# Clock_WR.net
KiCad netlist of a schematic drawn in Altium Designer
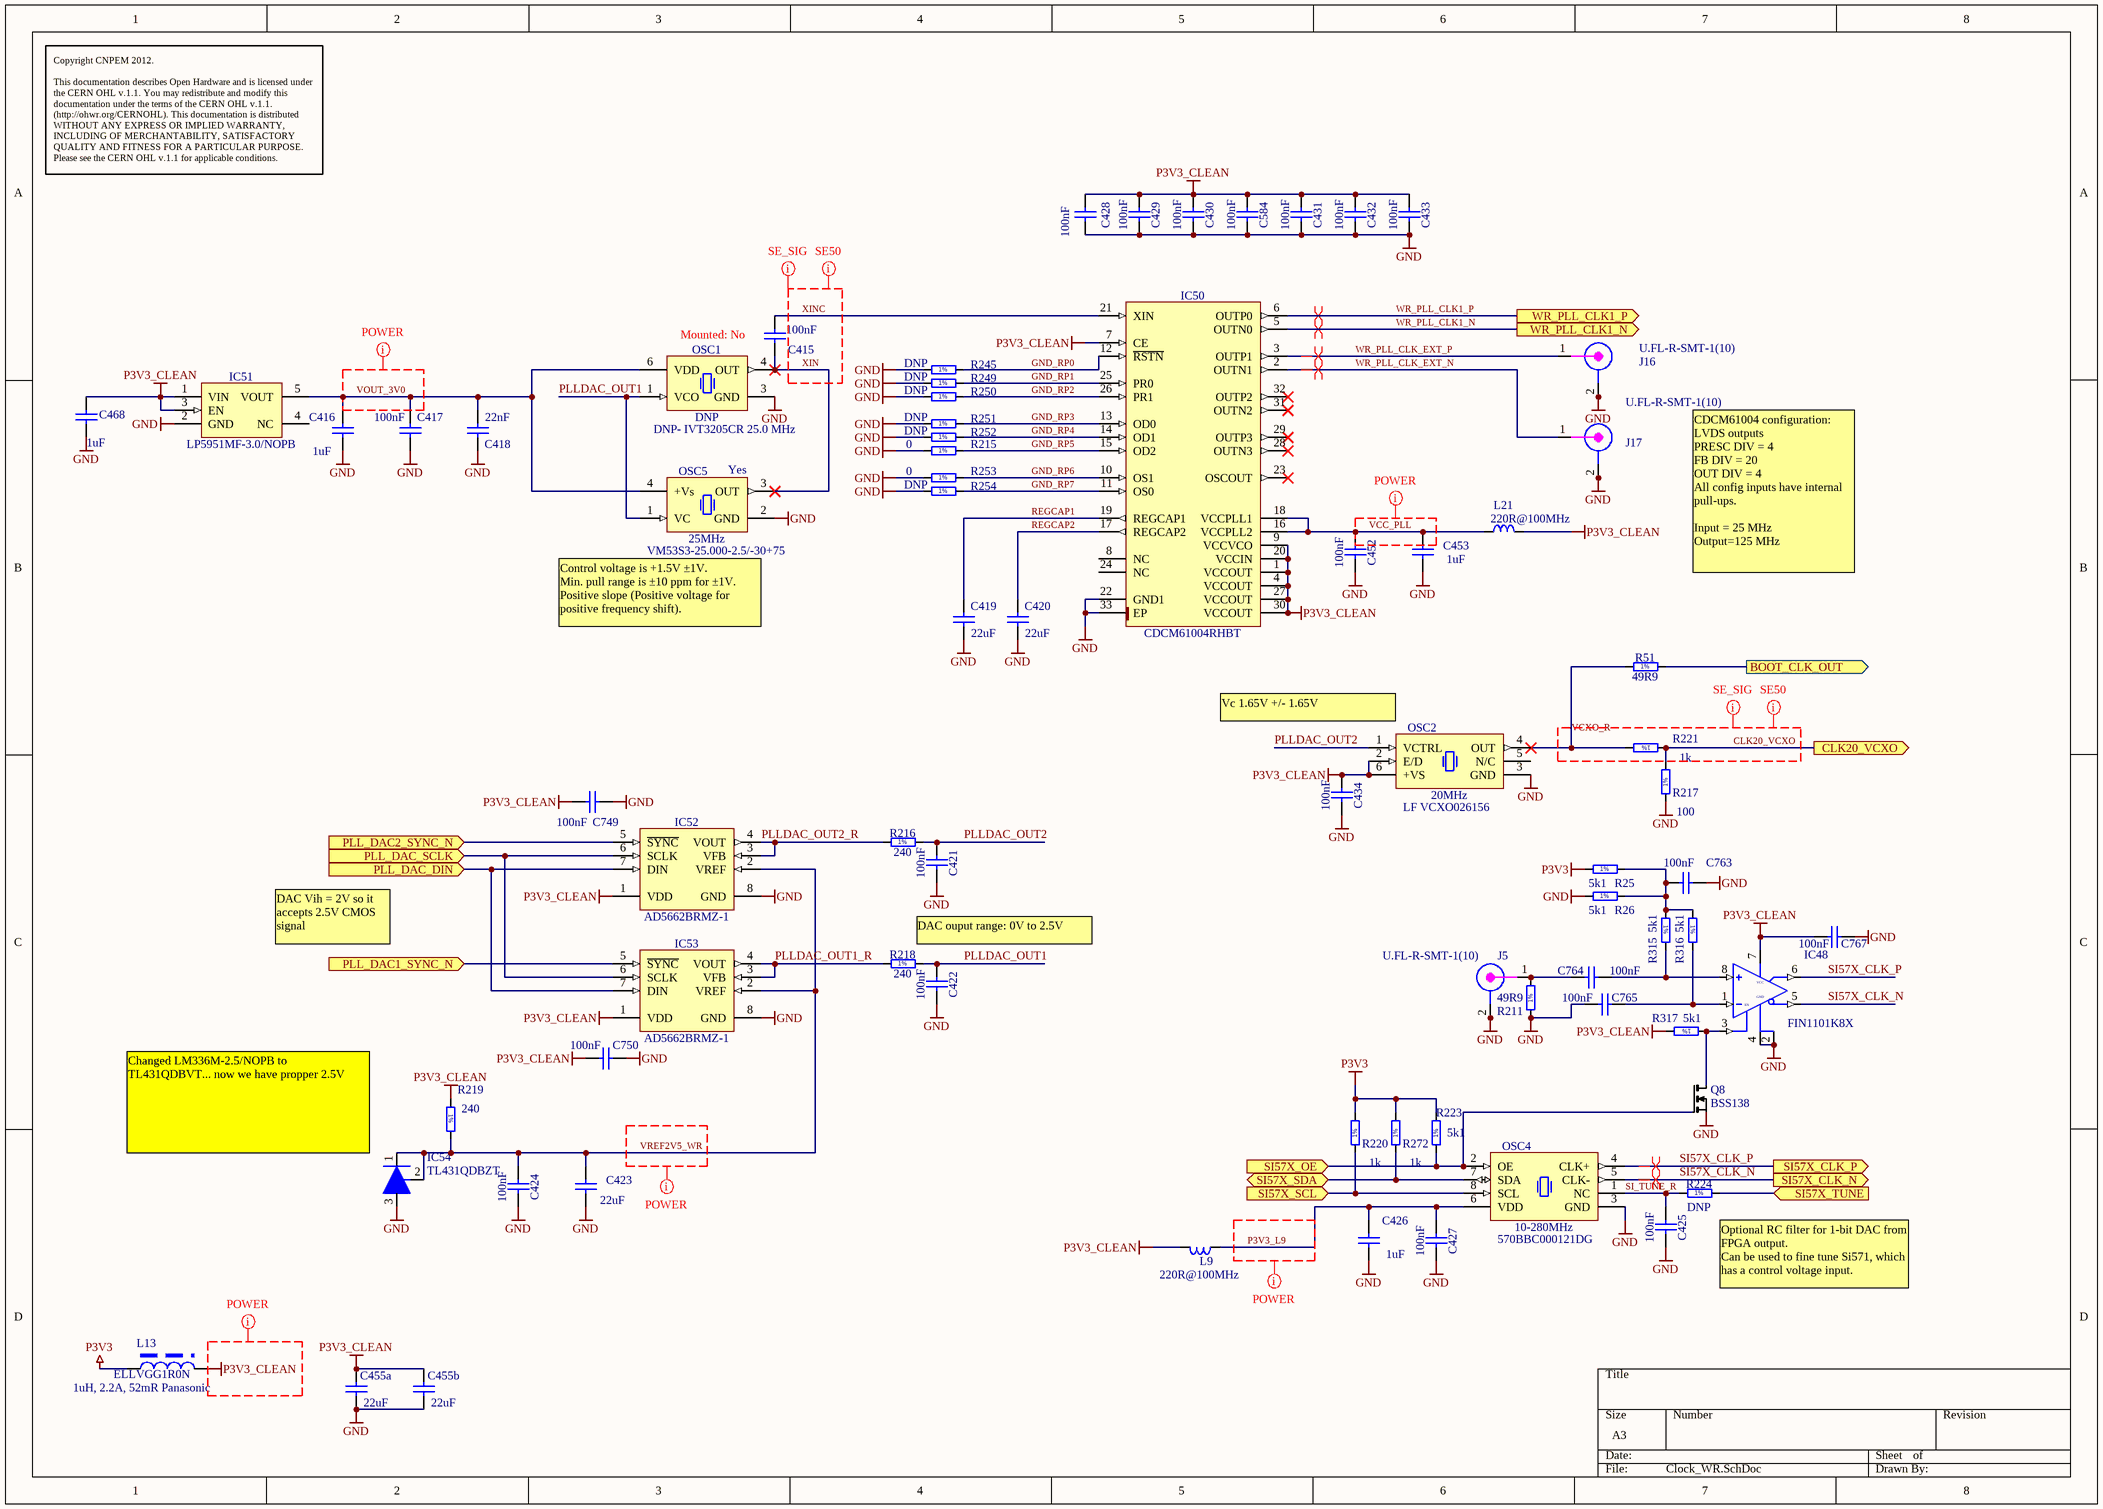
[diagram p0: Clock_WR.SchDoc]

(export (version "E")
  (design (tool "Eeschema 10.0.6"))
  (components
    (comp (ref "C415")
      (value "100nF")
      (footprint "CAPC0603X33N")
      (description "Non-polarised capacitor")
      (fields
        (field (name "PART NUMBER") "CC0201_100NF_6.3V_10%_X5R")
        (field (name "VOLTAGE") "6.3V")
        (field (name "AUTHOR") "CERN DEM JLC")
      )
      (libsource (lib "Capacitors") (part "Capacitor - non polarized"))
    )
    (comp (ref "C416")
      (value "1uF")
      (footprint "CAPC1608X87N")
      (description "Non-polarised capacitor")
      (fields
        (field (name "PART NUMBER") "CC0603_1UF_16V_10%_X7R")
        (field (name "VOLTAGE") "16V")
        (field (name "AUTHOR") "CERN DEM JLC")
      )
      (libsource (lib "Capacitors") (part "Capacitor - non polarized"))
    )
    (comp (ref "C417")
      (value "100nF")
      (footprint "CAPC0603X33N")
      (description "Non-polarised capacitor")
      (fields
        (field (name "PART NUMBER") "CC0201_100NF_6.3V_10%_X5R")
        (field (name "VOLTAGE") "6.3V")
        (field (name "AUTHOR") "CERN DEM JLC")
      )
      (libsource (lib "Capacitors") (part "Capacitor - non polarized"))
    )
    (comp (ref "C418")
      (value "22nF")
      (footprint "CAPC0603X33N")
      (description "Non-polarised capacitor")
      (fields
        (field (name "PART NUMBER") "CC0201_22NF_6.3V_10%_X5R")
        (field (name "VOLTAGE") "6.3V")
        (field (name "AUTHOR") "CERN DEM JLC")
      )
      (libsource (lib "Capacitors") (part "Capacitor - non polarized"))
    )
    (comp (ref "C419")
      (value "22uF")
      (footprint "CAPC3216X180N")
      (description "Non-polarised capacitor")
      (fields
        (field (name "PART NUMBER") "CC1206_22UF_10V_10%_X7R")
        (field (name "VOLTAGE") "10V")
        (field (name "AUTHOR") "CERN DEM JLC")
      )
      (libsource (lib "Capacitors") (part "Capacitor - non polarized"))
    )
    (comp (ref "C420")
      (value "22uF")
      (footprint "CAPC3216X180N")
      (description "Non-polarised capacitor")
      (fields
        (field (name "PART NUMBER") "CC1206_22UF_10V_10%_X7R")
        (field (name "VOLTAGE") "10V")
        (field (name "AUTHOR") "CERN DEM JLC")
      )
      (libsource (lib "Capacitors") (part "Capacitor - non polarized"))
    )
    (comp (ref "C421")
      (value "100nF")
      (footprint "CAPC0603X33N")
      (description "Non-polarised capacitor")
      (fields
        (field (name "PART NUMBER") "CC0201_100NF_6.3V_10%_X5R")
        (field (name "VOLTAGE") "6.3V")
        (field (name "AUTHOR") "CERN DEM JLC")
      )
      (libsource (lib "Capacitors") (part "Capacitor - non polarized"))
    )
    (comp (ref "C422")
      (value "100nF")
      (footprint "CAPC0603X33N")
      (description "Non-polarised capacitor")
      (fields
        (field (name "PART NUMBER") "CC0201_100NF_6.3V_10%_X5R")
        (field (name "VOLTAGE") "6.3V")
        (field (name "AUTHOR") "CERN DEM JLC")
      )
      (libsource (lib "Capacitors") (part "Capacitor - non polarized"))
    )
    (comp (ref "C423")
      (value "22uF")
      (footprint "CAPC3216X180N")
      (description "Non-polarised capacitor")
      (fields
        (field (name "PART NUMBER") "CC1206_22UF_10V_10%_X7R")
        (field (name "VOLTAGE") "10V")
        (field (name "AUTHOR") "CERN DEM JLC")
      )
      (libsource (lib "Capacitors") (part "Capacitor - non polarized"))
    )
    (comp (ref "C424")
      (value "100nF")
      (footprint "CAPC0603X33N")
      (description "Non-polarised capacitor")
      (fields
        (field (name "PART NUMBER") "CC0201_100NF_6.3V_10%_X5R")
        (field (name "VOLTAGE") "6.3V")
        (field (name "AUTHOR") "CERN DEM JLC")
      )
      (libsource (lib "Capacitors") (part "Capacitor - non polarized"))
    )
    (comp (ref "C425")
      (value "100nF")
      (footprint "CAPC0603X33N")
      (description "Non-polarised capacitor")
      (fields
        (field (name "PART NUMBER") "CC0201_100NF_6.3V_10%_X5R")
        (field (name "VOLTAGE") "6.3V")
        (field (name "AUTHOR") "CERN DEM JLC")
      )
      (libsource (lib "Capacitors") (part "Capacitor - non polarized"))
    )
    (comp (ref "C426")
      (value "1uF")
      (footprint "CAPC1608X87N")
      (description "Non-polarised capacitor")
      (fields
        (field (name "PART NUMBER") "CC0603_1UF_16V_10%_X7R")
        (field (name "VOLTAGE") "16V")
        (field (name "AUTHOR") "CERN DEM JLC")
      )
      (libsource (lib "Capacitors") (part "Capacitor - non polarized"))
    )
    (comp (ref "C427")
      (value "100nF")
      (footprint "CAPC0603X33N")
      (description "Non-polarised capacitor")
      (fields
        (field (name "PART NUMBER") "CC0201_100NF_6.3V_10%_X5R")
        (field (name "VOLTAGE") "6.3V")
        (field (name "AUTHOR") "CERN DEM JLC")
      )
      (libsource (lib "Capacitors") (part "Capacitor - non polarized"))
    )
    (comp (ref "C428")
      (value "100nF")
      (footprint "CAPC0603X33N")
      (description "Non-polarised capacitor")
      (fields
        (field (name "PART NUMBER") "CC0201_100NF_6.3V_10%_X5R")
        (field (name "VOLTAGE") "6.3V")
        (field (name "AUTHOR") "CERN DEM JLC")
      )
      (libsource (lib "Capacitors") (part "Capacitor - non polarized"))
    )
    (comp (ref "C429")
      (value "100nF")
      (footprint "CAPC0603X33N")
      (description "Non-polarised capacitor")
      (fields
        (field (name "PART NUMBER") "CC0201_100NF_6.3V_10%_X5R")
        (field (name "VOLTAGE") "6.3V")
        (field (name "AUTHOR") "CERN DEM JLC")
      )
      (libsource (lib "Capacitors") (part "Capacitor - non polarized"))
    )
    (comp (ref "C430")
      (value "100nF")
      (footprint "CAPC0603X33N")
      (description "Non-polarised capacitor")
      (fields
        (field (name "PART NUMBER") "CC0201_100NF_6.3V_10%_X5R")
        (field (name "VOLTAGE") "6.3V")
        (field (name "AUTHOR") "CERN DEM JLC")
      )
      (libsource (lib "Capacitors") (part "Capacitor - non polarized"))
    )
    (comp (ref "C431")
      (value "100nF")
      (footprint "CAPC0603X33N")
      (description "Non-polarised capacitor")
      (fields
        (field (name "PART NUMBER") "CC0201_100NF_6.3V_10%_X5R")
        (field (name "VOLTAGE") "6.3V")
        (field (name "AUTHOR") "CERN DEM JLC")
      )
      (libsource (lib "Capacitors") (part "Capacitor - non polarized"))
    )
    (comp (ref "C432")
      (value "100nF")
      (footprint "CAPC0603X33N")
      (description "Non-polarised capacitor")
      (fields
        (field (name "PART NUMBER") "CC0201_100NF_6.3V_10%_X5R")
        (field (name "VOLTAGE") "6.3V")
        (field (name "AUTHOR") "CERN DEM JLC")
      )
      (libsource (lib "Capacitors") (part "Capacitor - non polarized"))
    )
    (comp (ref "C433")
      (value "100nF")
      (footprint "CAPC0603X33N")
      (description "Non-polarised capacitor")
      (fields
        (field (name "PART NUMBER") "CC0201_100NF_6.3V_10%_X5R")
        (field (name "VOLTAGE") "6.3V")
        (field (name "AUTHOR") "CERN DEM JLC")
      )
      (libsource (lib "Capacitors") (part "Capacitor - non polarized"))
    )
    (comp (ref "C434")
      (value "100nF")
      (footprint "CAPC0603X33N")
      (description "Non-polarised capacitor")
      (fields
        (field (name "PART NUMBER") "CC0201_100NF_6.3V_10%_X5R")
        (field (name "VOLTAGE") "6.3V")
        (field (name "AUTHOR") "CERN DEM JLC")
      )
      (libsource (lib "Capacitors") (part "Capacitor - non polarized"))
    )
    (comp (ref "C452")
      (value "100nF")
      (footprint "CAPC0603X33N")
      (description "Non-polarised capacitor")
      (fields
        (field (name "PART NUMBER") "CC0201_100NF_6.3V_10%_X5R")
        (field (name "VOLTAGE") "6.3V")
        (field (name "AUTHOR") "CERN DEM JLC")
      )
      (libsource (lib "Capacitors") (part "Capacitor - non polarized"))
    )
    (comp (ref "C453")
      (value "1uF")
      (footprint "CAPC1608X87N")
      (description "Non-polarised capacitor")
      (fields
        (field (name "PART NUMBER") "CC0603_1UF_16V_10%_X7R")
        (field (name "VOLTAGE") "16V")
        (field (name "AUTHOR") "CERN DEM JLC")
      )
      (libsource (lib "Capacitors") (part "Capacitor - non polarized"))
    )
    (comp (ref "C455a")
      (value "22uF")
      (footprint "CAPC3216X180N")
      (description "Non-polarised capacitor")
      (fields
        (field (name "PART NUMBER") "CC1206_22UF_10V_10%_X7R")
        (field (name "VOLTAGE") "10V")
        (field (name "AUTHOR") "CERN DEM JLC")
      )
      (libsource (lib "Capacitors") (part "Capacitor - non polarized"))
    )
    (comp (ref "C455b")
      (value "22uF")
      (footprint "CAPC3216X180N")
      (description "Non-polarised capacitor")
      (fields
        (field (name "PART NUMBER") "CC1206_22UF_10V_10%_X7R")
        (field (name "VOLTAGE") "10V")
        (field (name "AUTHOR") "CERN DEM JLC")
      )
      (libsource (lib "Capacitors") (part "Capacitor - non polarized"))
    )
    (comp (ref "C468")
      (value "1uF")
      (footprint "CAPC1608X87N")
      (description "Non-polarised capacitor")
      (fields
        (field (name "PART NUMBER") "CC0603_1UF_16V_10%_X7R")
        (field (name "VOLTAGE") "16V")
        (field (name "AUTHOR") "CERN DEM JLC")
      )
      (libsource (lib "Capacitors") (part "Capacitor - non polarized"))
    )
    (comp (ref "C584")
      (value "100nF")
      (footprint "CAPC0603X33N")
      (description "Non-polarised capacitor")
      (fields
        (field (name "PART NUMBER") "CC0201_100NF_6.3V_10%_X5R")
        (field (name "VOLTAGE") "6.3V")
        (field (name "AUTHOR") "CERN DEM JLC")
      )
      (libsource (lib "Capacitors") (part "Capacitor - non polarized"))
    )
    (comp (ref "C749")
      (value "100nF")
      (footprint "CAPC0603X33N")
      (description "Non-polarised capacitor")
      (fields
        (field (name "PART NUMBER") "CC0201_100NF_6.3V_10%_X5R")
        (field (name "VOLTAGE") "6.3V")
        (field (name "AUTHOR") "CERN DEM JLC")
      )
      (libsource (lib "Capacitors") (part "Capacitor - non polarized"))
    )
    (comp (ref "C750")
      (value "100nF")
      (footprint "CAPC0603X33N")
      (description "Non-polarised capacitor")
      (fields
        (field (name "PART NUMBER") "CC0201_100NF_6.3V_10%_X5R")
        (field (name "VOLTAGE") "6.3V")
        (field (name "AUTHOR") "CERN DEM JLC")
      )
      (libsource (lib "Capacitors") (part "Capacitor - non polarized"))
    )
    (comp (ref "C763")
      (value "100nF")
      (footprint "CAPC0603X33N")
      (description "Non-polarised capacitor")
      (fields
        (field (name "PART NUMBER") "CC0201_100NF_6.3V_10%_X5R")
        (field (name "VOLTAGE") "6.3V")
        (field (name "AUTHOR") "CERN DEM JLC")
      )
      (libsource (lib "Capacitors") (part "Capacitor - non polarized"))
    )
    (comp (ref "C764")
      (value "100nF")
      (footprint "CAPC0603X33N")
      (description "Non-polarised capacitor")
      (fields
        (field (name "PART NUMBER") "CC0201_100NF_6.3V_10%_X5R")
        (field (name "VOLTAGE") "6.3V")
        (field (name "AUTHOR") "CERN DEM JLC")
      )
      (libsource (lib "Capacitors") (part "Capacitor - non polarized"))
    )
    (comp (ref "C765")
      (value "100nF")
      (footprint "CAPC0603X33N")
      (description "Non-polarised capacitor")
      (fields
        (field (name "PART NUMBER") "CC0201_100NF_6.3V_10%_X5R")
        (field (name "VOLTAGE") "6.3V")
        (field (name "AUTHOR") "CERN DEM JLC")
      )
      (libsource (lib "Capacitors") (part "Capacitor - non polarized"))
    )
    (comp (ref "C767")
      (value "100nF")
      (footprint "CAPC0603X33N")
      (description "Non-polarised capacitor")
      (fields
        (field (name "PART NUMBER") "CC0201_100NF_6.3V_10%_X5R")
        (field (name "VOLTAGE") "6.3V")
        (field (name "AUTHOR") "CERN DEM JLC")
      )
      (libsource (lib "Capacitors") (part "Capacitor - non polarized"))
    )
    (comp (ref "IC48")
      (value "FIN1101K8X")
      (footprint "US8")
      (description "LVDS TO LVDS repeater3.3V")
      (libsource (lib "AMC_FMC_Carrier") (part "IFC_FIN1101K8X"))
    )
    (comp (ref "IC50")
      (value "CDCM61004RHBT")
      (footprint "QFN50P500X500X100-33N-S355")
      (description "Four Output, Integrated VCO, Low-Jitter Clock Generator")
      (fields (field (name "MANUFACTURER") "TEXAS INSTRUMENTS") (field (name "AUTHOR") "CERN DEM JLC"))
      (libsource (lib "ICs And Semiconductors") (part "CDCM61004RHB"))
    )
    (comp (ref "IC51")
      (value "LP5951MF-3.0/NOPB")
      (footprint "SOT95P284X122-5N")
      (description "150mA Micropower Low-Dropout CMOS Voltage Regulator")
      (fields (field (name "MANUFACTURER") "NATIONAL SEMICONDUCTOR") (field (name "AUTHOR") "CERN DEM JLC"))
      (libsource (lib "ICs And Semiconductors") (part "LP5951"))
    )
    (comp (ref "IC52")
      (value "AD5662BRMZ-1")
      (footprint "SOP65P490X110-8N")
      (description "2.7V to 5.5V, 250uA, Rail-to-Rail Output 16-Bit nanoDAC")
      (fields (field (name "MANUFACTURER") "ANALOG DEVICES") (field (name "AUTHOR") "CERN DEM JLC"))
      (libsource (lib "ICs And Semiconductors") (part "AD5662"))
    )
    (comp (ref "IC53")
      (value "AD5662BRMZ-1")
      (footprint "SOP65P490X110-8N")
      (description "2.7V to 5.5V, 250uA, Rail-to-Rail Output 16-Bit nanoDAC")
      (fields (field (name "MANUFACTURER") "ANALOG DEVICES") (field (name "AUTHOR") "CERN DEM JLC"))
      (libsource (lib "ICs And Semiconductors") (part "AD5662"))
    )
    (comp (ref "IC54")
      (value "TL431QDBZT")
      (footprint "SOT-23")
      (description "2.5V ADJ Voltage reference")
      (libsource (lib "LIBRARY_SCH") (part "REF_TL431_SOT23"))
    )
    (comp (ref "J5")
      (value "U.FL-R-SMT-1(10)")
      (footprint "CON_UFL_HIROSE_RECEPTACLE")
      (description "UFL")
      (libsource (lib "LIBRARY_SCH") (part "CON_UFL_SMD"))
    )
    (comp (ref "J16")
      (value "U.FL-R-SMT-1(10)")
      (footprint "CON_UFL_HIROSE_RECEPTACLE")
      (description "UFL")
      (libsource (lib "LIBRARY_SCH") (part "CON_UFL_SMD"))
    )
    (comp (ref "J17")
      (value "U.FL-R-SMT-1(10)")
      (footprint "CON_UFL_HIROSE_RECEPTACLE")
      (description "UFL")
      (libsource (lib "LIBRARY_SCH") (part "CON_UFL_SMD"))
    )
    (comp (ref "L9")
      (value "220R@100MHz")
      (footprint "INDC2012X105N")
      (description "Inductor")
      (fields
        (field (name "PART NUMBER") "IND0805_MURATA_BLM21PG221SN1D")
        (field (name "POWER") "2A")
        (field (name "AUTHOR") "CERN DEM JLC")
      )
      (libsource (lib "Inductors & Transformers") (part "Inductor"))
    )
    (comp (ref "L13")
      (value "ELLVGG1R0N")
      (footprint "L_ELLVGG2R2N")
      (description "2.2uH, 1.4A, 92mR Panasonic")
      (fields (field (name "ALTIUM_UNNAMED_1") "1uH, 2.2A, 52mR Panasonic"))
      (libsource (lib "LIBRARY_SCH") (part "L_CHOKE_ELLVGG"))
    )
    (comp (ref "L21")
      (value "220R@100MHz")
      (footprint "INDC2012X105N")
      (description "Inductor")
      (fields
        (field (name "PART NUMBER") "IND0805_MURATA_BLM21PG221SN1D")
        (field (name "POWER") "2A")
        (field (name "AUTHOR") "CERN DEM JLC")
      )
      (libsource (lib "Inductors & Transformers") (part "Inductor"))
    )
    (comp (ref "OSC1")
      (value "DNP")
      (footprint "OSC_RAKON_IVT3200C")
      (description "Oscillator 4 pins 1=VCO 3=GND 4=OUT 6=VDC")
      (fields
        (field (name "PART NUMBER") "OSC_25MHZ_RAKON_IVT3205CR")
        (field (name "MANUFACTURER") "RAKON")
        (field (name "MANUFACTURER PART NUMBER") "DNP- IVT3205CR 25.0 MHz")
        (field (name "MOUNTED") "No")
        (field (name "AUTHOR") "CERN DEM JLC")
      )
      (libsource (lib "ICs And Semiconductors") (part "Oscillator 1VCO 3GND 4OUT 6VCC"))
    )
    (comp (ref "OSC2")
      (value "20MHz")
      (footprint "OSC_IQD_CFPV-45")
      (description "3.3V ±100ppm 15pF HCMOS Tri-State Surface Mount Voltage Controlled Oscillator VCXO (CFPV-45 Serie)")
      (fields
        (field (name "PART NUMBER") "OSC_20MHZ_IQD_LF VCXO026156")
        (field (name "MANUFACTURER") "IQD FREQUENCY PRODUCTS")
        (field (name "MANUFACTURER PART NUMBER") "LF VCXO026156")
        (field (name "AUTHOR") "CERN DEM JLC")
      )
      (libsource (lib "ICs And Semiconductors") (part "Oscillator IQD_CFPV-45"))
    )
    (comp (ref "OSC4")
      (value "10-280MHz")
      (footprint "OSC_SILICON-LAB_SI570")
      (description "Any-Rate I2C Programmable XO Oscillator Si570 Serie")
      (fields
        (field (name "PART NUMBER") "OSC_10-280MHZ_SILICON-LAB_Si570BBC000121DG")
        (field (name "MANUFACTURER") "SILICON LABS")
        (field (name "MANUFACTURER PART NUMBER") "570BBC000121DG")
        (field (name "AUTHOR") "CERN DEM JLC")
      )
      (libsource (lib "ICs And Semiconductors") (part "Oscillator SILICON-LAB_Si570"))
    )
    (comp (ref "OSC5")
      (value "25MHz")
      (footprint "OSCCC320X500X160-4N")
      (description "Oscillator 4 pins 1=VC 2=GND 3=OUT 4=+Vs")
      (fields
        (field (name "PART NUMBER") "OSC_25MHZ_MERCURY_VM53S3-25.000-2.5/-30+75")
        (field (name "MANUFACTURER") "MERCURY ELECTRONICS")
        (field (name "MANUFACTURER PART NUMBER") "VM53S3-25.000-2.5/-30+75")
        (field (name "MOUNTED") "Yes")
        (field (name "AUTHOR") "CERN DEM JLC")
      )
      (libsource (lib "ICs And Semiconductors") (part "Oscillator 1VC 2GND 3OUT 4+Vs"))
    )
    (comp (ref "Q8")
      (value "BSS138")
      (footprint "SOT95P251X112-3N")
      (libsource (lib "LIBRARY_SCH") (part "Q_BSS138"))
    )
    (comp (ref "R25")
      (value "5k1")
      (footprint "RESC1608X55N")
      (description "Resistor - 1%")
      (fields
        (field (name "PART NUMBER") "R0603_5K1_1%_0.1W_100PPM")
        (field (name "POWER") "0.1W")
        (field (name "AUTHOR") "CERN DEM JLC")
      )
      (libsource (lib "Resistors") (part "Resistor - 1%"))
    )
    (comp (ref "R26")
      (value "5k1")
      (footprint "RESC1608X55N")
      (description "Resistor - 1%")
      (fields
        (field (name "PART NUMBER") "R0603_5K1_1%_0.1W_100PPM")
        (field (name "POWER") "0.1W")
        (field (name "AUTHOR") "CERN DEM JLC")
      )
      (libsource (lib "Resistors") (part "Resistor - 1%"))
    )
    (comp (ref "R51")
      (value "49R9")
      (footprint "RESC1005X40N")
      (description "Resistor - 1%")
      (fields
        (field (name "PART NUMBER") "R0402_49R9_1%_0.0625W_100PPM")
        (field (name "POWER") "0.0625W")
        (field (name "AUTHOR") "CERN DEM JLC")
      )
      (libsource (lib "Resistors") (part "Resistor - 1%"))
    )
    (comp (ref "R211")
      (value "49R9")
      (footprint "RESC1005X40N")
      (description "Resistor - 1%")
      (fields
        (field (name "PART NUMBER") "R0402_49R9_1%_0.0625W_100PPM")
        (field (name "POWER") "0.0625W")
        (field (name "AUTHOR") "CERN DEM JLC")
      )
      (libsource (lib "Resistors") (part "Resistor - 1%"))
    )
    (comp (ref "R215")
      (value "0")
      (footprint "RESC1005X40N")
      (description "Resistor - 1%")
      (fields
        (field (name "PART NUMBER") "R0402_0R_JUMPER")
        (field (name "MANUFACTURER") "GENERIC")
        (field (name "AUTHOR") "CERN DEM JLC")
      )
      (libsource (lib "Resistors") (part "Resistor - 1%"))
    )
    (comp (ref "R216")
      (value "240")
      (footprint "RESC1005X40N")
      (description "Resistor - 1%")
      (fields
        (field (name "PART NUMBER") "R0402_240R_1%_0.0625W_100PPM")
        (field (name "POWER") "0.0625W")
        (field (name "AUTHOR") "CERN DEM JLC")
      )
      (libsource (lib "Resistors") (part "Resistor - 1%"))
    )
    (comp (ref "R217")
      (value "100")
      (footprint "RESC1005X40N")
      (description "Resistor - 1%")
      (fields
        (field (name "PART NUMBER") "R0402_100R_1%_0.0625W_100PPM")
        (field (name "POWER") "0.0625W")
        (field (name "AUTHOR") "CERN DEM JLC")
      )
      (libsource (lib "Resistors") (part "Resistor - 1%"))
    )
    (comp (ref "R218")
      (value "240")
      (footprint "RESC1005X40N")
      (description "Resistor - 1%")
      (fields
        (field (name "PART NUMBER") "R0402_240R_1%_0.0625W_100PPM")
        (field (name "POWER") "0.0625W")
        (field (name "AUTHOR") "CERN DEM JLC")
      )
      (libsource (lib "Resistors") (part "Resistor - 1%"))
    )
    (comp (ref "R219")
      (value "240")
      (footprint "RESC1005X40N")
      (description "Resistor - 1%")
      (fields
        (field (name "PART NUMBER") "R0402_240R_1%_0.0625W_100PPM")
        (field (name "POWER") "0.0625W")
        (field (name "AUTHOR") "CERN DEM JLC")
      )
      (libsource (lib "Resistors") (part "Resistor - 1%"))
    )
    (comp (ref "R220")
      (value "1k")
      (footprint "RESC1005X40N")
      (description "Resistor - 1%")
      (fields
        (field (name "PART NUMBER") "R0402_1K_1%_0.0625W_100PPM")
        (field (name "POWER") "0.0625W")
        (field (name "AUTHOR") "CERN DEM JLC")
      )
      (libsource (lib "Resistors") (part "Resistor - 1%"))
    )
    (comp (ref "R221")
      (value "1k")
      (footprint "RESC1005X40N")
      (description "Resistor - 1%")
      (fields
        (field (name "PART NUMBER") "R0402_1K_1%_0.0625W_100PPM")
        (field (name "POWER") "0.0625W")
        (field (name "AUTHOR") "CERN DEM JLC")
      )
      (libsource (lib "Resistors") (part "Resistor - 1%"))
    )
    (comp (ref "R223")
      (value "5k1")
      (footprint "RESC1608X55N")
      (description "Resistor - 1%")
      (fields
        (field (name "PART NUMBER") "R0603_5K1_1%_0.1W_100PPM")
        (field (name "POWER") "0.1W")
        (field (name "AUTHOR") "CERN DEM JLC")
      )
      (libsource (lib "Resistors") (part "Resistor - 1%"))
    )
    (comp (ref "R224")
      (value "DNP")
      (footprint "RESC1005X40N")
      (description "Resistor - 1%")
      (fields
        (field (name "PART NUMBER") "R0402_100R_1%_0.0625W_100PPM")
        (field (name "POWER") "0.0625W")
        (field (name "AUTHOR") "CERN DEM JLC")
      )
      (libsource (lib "Resistors") (part "Resistor - 1%"))
    )
    (comp (ref "R245")
      (value "DNP")
      (footprint "RESC1005X40N")
      (description "Resistor - 1%")
      (fields
        (field (name "PART NUMBER") "R0402_0R_JUMPER")
        (field (name "MANUFACTURER") "GENERIC")
        (field (name "AUTHOR") "CERN DEM JLC")
      )
      (libsource (lib "Resistors") (part "Resistor - 1%"))
    )
    (comp (ref "R249")
      (value "DNP")
      (footprint "RESC1005X40N")
      (description "Resistor - 1%")
      (fields
        (field (name "PART NUMBER") "R0402_0R_JUMPER")
        (field (name "MANUFACTURER") "GENERIC")
        (field (name "AUTHOR") "CERN DEM JLC")
      )
      (libsource (lib "Resistors") (part "Resistor - 1%"))
    )
    (comp (ref "R250")
      (value "DNP")
      (footprint "RESC1005X40N")
      (description "Resistor - 1%")
      (fields
        (field (name "PART NUMBER") "R0402_0R_JUMPER")
        (field (name "MANUFACTURER") "GENERIC")
        (field (name "AUTHOR") "CERN DEM JLC")
      )
      (libsource (lib "Resistors") (part "Resistor - 1%"))
    )
    (comp (ref "R251")
      (value "DNP")
      (footprint "RESC1005X40N")
      (description "Resistor - 1%")
      (fields
        (field (name "PART NUMBER") "R0402_0R_JUMPER")
        (field (name "MANUFACTURER") "GENERIC")
        (field (name "AUTHOR") "CERN DEM JLC")
      )
      (libsource (lib "Resistors") (part "Resistor - 1%"))
    )
    (comp (ref "R252")
      (value "DNP")
      (footprint "RESC1005X40N")
      (description "Resistor - 1%")
      (fields
        (field (name "PART NUMBER") "R0402_0R_JUMPER")
        (field (name "MANUFACTURER") "GENERIC")
        (field (name "AUTHOR") "CERN DEM JLC")
      )
      (libsource (lib "Resistors") (part "Resistor - 1%"))
    )
    (comp (ref "R253")
      (value "0")
      (footprint "RESC1005X40N")
      (description "Resistor - 1%")
      (fields
        (field (name "PART NUMBER") "R0402_0R_JUMPER")
        (field (name "MANUFACTURER") "GENERIC")
        (field (name "AUTHOR") "CERN DEM JLC")
      )
      (libsource (lib "Resistors") (part "Resistor - 1%"))
    )
    (comp (ref "R254")
      (value "DNP")
      (footprint "RESC1005X40N")
      (description "Resistor - 1%")
      (fields
        (field (name "PART NUMBER") "R0402_0R_JUMPER")
        (field (name "MANUFACTURER") "GENERIC")
        (field (name "AUTHOR") "CERN DEM JLC")
      )
      (libsource (lib "Resistors") (part "Resistor - 1%"))
    )
    (comp (ref "R272")
      (value "1k")
      (footprint "RESC1005X40N")
      (description "Resistor - 1%")
      (fields
        (field (name "PART NUMBER") "R0402_1K_1%_0.0625W_100PPM")
        (field (name "POWER") "0.0625W")
        (field (name "AUTHOR") "CERN DEM JLC")
      )
      (libsource (lib "Resistors") (part "Resistor - 1%"))
    )
    (comp (ref "R315")
      (value "5k1")
      (footprint "RESC1608X55N")
      (description "Resistor - 1%")
      (fields
        (field (name "PART NUMBER") "R0603_5K1_1%_0.1W_100PPM")
        (field (name "POWER") "0.1W")
        (field (name "AUTHOR") "CERN DEM JLC")
      )
      (libsource (lib "Resistors") (part "Resistor - 1%"))
    )
    (comp (ref "R316")
      (value "5k1")
      (footprint "RESC1608X55N")
      (description "Resistor - 1%")
      (fields
        (field (name "PART NUMBER") "R0603_5K1_1%_0.1W_100PPM")
        (field (name "POWER") "0.1W")
        (field (name "AUTHOR") "CERN DEM JLC")
      )
      (libsource (lib "Resistors") (part "Resistor - 1%"))
    )
    (comp (ref "R317")
      (value "5k1")
      (footprint "RESC1608X55N")
      (description "Resistor - 1%")
      (fields
        (field (name "PART NUMBER") "R0603_5K1_1%_0.1W_100PPM")
        (field (name "POWER") "0.1W")
        (field (name "AUTHOR") "CERN DEM JLC")
      )
      (libsource (lib "Resistors") (part "Resistor - 1%"))
    )
  )
  (nets
    (net (code "1") (name "/BOOT_CLK_OUT") (class "Default")
      (node (ref "R51") (pin "2") (pinfunction "2_2") (pintype "passive"))
    )
    (net (code "2") (name "/CLK20_VCXO") (class "Default")
      (node (ref "R217") (pin "2") (pinfunction "2_2") (pintype "passive"))
      (node (ref "R221") (pin "1") (pinfunction "1_1") (pintype "passive"))
    )
    (net (code "3") (name "/GND_RP0") (class "Default")
      (node (ref "IC50") (pin "12") (pinfunction "~{RSTN}_12") (pintype "input"))
      (node (ref "R245") (pin "2") (pinfunction "2_2") (pintype "passive"))
    )
    (net (code "4") (name "/GND_RP1") (class "Default")
      (node (ref "IC50") (pin "25") (pinfunction "PR0_25") (pintype "input"))
      (node (ref "R249") (pin "2") (pinfunction "2_2") (pintype "passive"))
    )
    (net (code "5") (name "/GND_RP2") (class "Default")
      (node (ref "IC50") (pin "26") (pinfunction "PR1_26") (pintype "input"))
      (node (ref "R250") (pin "2") (pinfunction "2_2") (pintype "passive"))
    )
    (net (code "6") (name "/GND_RP3") (class "Default")
      (node (ref "IC50") (pin "13") (pinfunction "OD0_13") (pintype "input"))
      (node (ref "R251") (pin "2") (pinfunction "2_2") (pintype "passive"))
    )
    (net (code "7") (name "/GND_RP4") (class "Default")
      (node (ref "IC50") (pin "14") (pinfunction "OD1_14") (pintype "input"))
      (node (ref "R252") (pin "2") (pinfunction "2_2") (pintype "passive"))
    )
    (net (code "8") (name "/GND_RP5") (class "Default")
      (node (ref "IC50") (pin "15") (pinfunction "OD2_15") (pintype "input"))
      (node (ref "R215") (pin "2") (pinfunction "2_2") (pintype "passive"))
    )
    (net (code "9") (name "/GND_RP6") (class "Default")
      (node (ref "IC50") (pin "10") (pinfunction "OS1_10") (pintype "input"))
      (node (ref "R253") (pin "2") (pinfunction "2_2") (pintype "passive"))
    )
    (net (code "10") (name "/GND_RP7") (class "Default")
      (node (ref "IC50") (pin "11") (pinfunction "OS0_11") (pintype "input"))
      (node (ref "R254") (pin "2") (pinfunction "2_2") (pintype "passive"))
    )
    (net (code "11") (name "/P3V3_L9") (class "Default")
      (node (ref "C426") (pin "2") (pinfunction "2_2") (pintype "passive"))
      (node (ref "C427") (pin "1") (pinfunction "1_1") (pintype "passive"))
      (node (ref "L9") (pin "1") (pinfunction "1_1") (pintype "passive"))
      (node (ref "OSC4") (pin "6") (pinfunction "VDD_6") (pintype "power_in"))
    )
    (net (code "12") (name "/PLLDAC_OUT1") (class "Default")
      (node (ref "C422") (pin "1") (pinfunction "1_1") (pintype "passive"))
      (node (ref "OSC1") (pin "1") (pinfunction "VCO_1") (pintype "input"))
      (node (ref "OSC5") (pin "1") (pinfunction "VC_1") (pintype "input"))
      (node (ref "R218") (pin "2") (pinfunction "2_2") (pintype "passive"))
    )
    (net (code "13") (name "/PLLDAC_OUT1_R") (class "Default")
      (node (ref "IC53") (pin "3") (pinfunction "VFB_3") (pintype "input"))
      (node (ref "IC53") (pin "4") (pinfunction "VOUT_4") (pintype "output"))
      (node (ref "R218") (pin "1") (pinfunction "1_1") (pintype "passive"))
    )
    (net (code "14") (name "/PLLDAC_OUT2") (class "Default")
      (node (ref "C421") (pin "1") (pinfunction "1_1") (pintype "passive"))
      (node (ref "OSC2") (pin "1") (pinfunction "VCTRL_1") (pintype "input"))
      (node (ref "R216") (pin "2") (pinfunction "2_2") (pintype "passive"))
    )
    (net (code "15") (name "/PLLDAC_OUT2_R") (class "Default")
      (node (ref "IC52") (pin "3") (pinfunction "VFB_3") (pintype "input"))
      (node (ref "IC52") (pin "4") (pinfunction "VOUT_4") (pintype "output"))
      (node (ref "R216") (pin "1") (pinfunction "1_1") (pintype "passive"))
    )
    (net (code "16") (name "/PLL_DAC1_SYNC_N") (class "Default")
      (node (ref "IC53") (pin "5") (pinfunction "~{SYNC}_5") (pintype "input"))
    )
    (net (code "17") (name "/PLL_DAC2_SYNC_N") (class "Default")
      (node (ref "IC52") (pin "5") (pinfunction "~{SYNC}_5") (pintype "input"))
    )
    (net (code "18") (name "/PLL_DAC_DIN") (class "Default")
      (node (ref "IC52") (pin "7") (pinfunction "DIN_7") (pintype "input"))
      (node (ref "IC53") (pin "7") (pinfunction "DIN_7") (pintype "input"))
    )
    (net (code "19") (name "/PLL_DAC_SCLK") (class "Default")
      (node (ref "IC52") (pin "6") (pinfunction "SCLK_6") (pintype "input"))
      (node (ref "IC53") (pin "6") (pinfunction "SCLK_6") (pintype "input"))
    )
    (net (code "20") (name "/REGCAP1") (class "Default")
      (node (ref "C419") (pin "2") (pinfunction "2_2") (pintype "passive"))
      (node (ref "IC50") (pin "19") (pinfunction "REGCAP1_19") (pintype "output"))
    )
    (net (code "21") (name "/REGCAP2") (class "Default")
      (node (ref "C420") (pin "2") (pinfunction "2_2") (pintype "passive"))
      (node (ref "IC50") (pin "17") (pinfunction "REGCAP2_17") (pintype "output"))
    )
    (net (code "22") (name "/SI57X_CLK_N") (class "Default")
      (node (ref "IC48") (pin "5") (pinfunction "~{Q}_5") (pintype "output"))
      (node (ref "OSC4") (pin "5") (pinfunction "CLK-_5") (pintype "output"))
    )
    (net (code "23") (name "/SI57X_CLK_P") (class "Default")
      (node (ref "IC48") (pin "6") (pinfunction "Q_6") (pintype "output"))
      (node (ref "OSC4") (pin "4") (pinfunction "CLK+_4") (pintype "output"))
    )
    (net (code "24") (name "/SI57X_OE") (class "Default")
      (node (ref "OSC4") (pin "2") (pinfunction "OE_2") (pintype "input"))
      (node (ref "Q8") (pin "1") (pinfunction "G_1") (pintype "input"))
      (node (ref "R223") (pin "1") (pinfunction "1_1") (pintype "passive"))
    )
    (net (code "25") (name "/SI57X_SCL") (class "Default")
      (node (ref "OSC4") (pin "8") (pinfunction "SCL_8") (pintype "input"))
      (node (ref "R220") (pin "1") (pinfunction "1_1") (pintype "passive"))
    )
    (net (code "26") (name "/SI57X_SDA") (class "Default")
      (node (ref "OSC4") (pin "7") (pinfunction "SDA_7") (pintype "bidirectional"))
      (node (ref "R272") (pin "1") (pinfunction "1_1") (pintype "passive"))
    )
    (net (code "27") (name "/SI57X_TUNE") (class "Default")
      (node (ref "R224") (pin "2") (pinfunction "2_2") (pintype "passive"))
    )
    (net (code "28") (name "/SI_TUNE_R") (class "Default")
      (node (ref "C425") (pin "1") (pinfunction "1_1") (pintype "passive"))
      (node (ref "OSC4") (pin "1") (pinfunction "NC_1") (pintype "passive"))
      (node (ref "R224") (pin "1") (pinfunction "1_1") (pintype "passive"))
    )
    (net (code "29") (name "/VCC_PLL") (class "Default")
      (node (ref "C452") (pin "1") (pinfunction "1_1") (pintype "passive"))
      (node (ref "C453") (pin "2") (pinfunction "2_2") (pintype "passive"))
      (node (ref "IC50") (pin "16") (pinfunction "VCCPLL2_16") (pintype "power_in"))
      (node (ref "IC50") (pin "18") (pinfunction "VCCPLL1_18") (pintype "power_in"))
      (node (ref "L21") (pin "1") (pinfunction "1_1") (pintype "passive"))
    )
    (net (code "30") (name "/VCXO_R") (class "Default")
      (node (ref "OSC2") (pin "4") (pinfunction "OUT_4") (pintype "output"))
      (node (ref "R221") (pin "2") (pinfunction "2_2") (pintype "passive"))
      (node (ref "R51") (pin "1") (pinfunction "1_1") (pintype "passive"))
    )
    (net (code "31") (name "/VOUT_3V0") (class "Default")
      (node (ref "C416") (pin "2") (pinfunction "2_2") (pintype "passive"))
      (node (ref "C417") (pin "1") (pinfunction "1_1") (pintype "passive"))
      (node (ref "C418") (pin "2") (pinfunction "2_2") (pintype "passive"))
      (node (ref "IC51") (pin "5") (pinfunction "VOUT_5") (pintype "power_in"))
      (node (ref "OSC1") (pin "6") (pinfunction "VDD_6") (pintype "power_in"))
      (node (ref "OSC5") (pin "4") (pinfunction "+Vs_4") (pintype "power_in"))
    )
    (net (code "32") (name "/VREF2V5_WR") (class "Default")
      (node (ref "C423") (pin "2") (pinfunction "2_2") (pintype "passive"))
      (node (ref "C424") (pin "1") (pinfunction "1_1") (pintype "passive"))
      (node (ref "IC52") (pin "2") (pinfunction "VREF_2") (pintype "input"))
      (node (ref "IC53") (pin "2") (pinfunction "VREF_2") (pintype "input"))
      (node (ref "IC54") (pin "1") (pinfunction "I/O_1") (pintype "passive"))
      (node (ref "IC54") (pin "2") (pinfunction "REF_2") (pintype "passive"))
      (node (ref "R219") (pin "2") (pinfunction "2_2") (pintype "passive"))
    )
    (net (code "33") (name "/WR_PLL_CLK1_N") (class "Default")
      (node (ref "IC50") (pin "5") (pinfunction "OUTN0_5") (pintype "output"))
    )
    (net (code "34") (name "/WR_PLL_CLK1_P") (class "Default")
      (node (ref "IC50") (pin "6") (pinfunction "OUTP0_6") (pintype "output"))
    )
    (net (code "35") (name "/WR_PLL_CLK_EXT_N") (class "Default")
      (node (ref "IC50") (pin "2") (pinfunction "OUTN1_2") (pintype "output"))
      (node (ref "J17") (pin "1") (pintype "passive"))
    )
    (net (code "36") (name "/WR_PLL_CLK_EXT_P") (class "Default")
      (node (ref "IC50") (pin "3") (pinfunction "OUTP1_3") (pintype "output"))
      (node (ref "J16") (pin "1") (pintype "passive"))
    )
    (net (code "37") (name "/XIN") (class "Default")
      (node (ref "C415") (pin "1") (pinfunction "1_1") (pintype "passive"))
      (node (ref "OSC1") (pin "4") (pinfunction "OUT_4") (pintype "output"))
      (node (ref "OSC5") (pin "3") (pinfunction "OUT_3") (pintype "output"))
    )
    (net (code "38") (name "/XINC") (class "Default")
      (node (ref "C415") (pin "2") (pinfunction "2_2") (pintype "passive"))
      (node (ref "IC50") (pin "21") (pinfunction "XIN_21") (pintype "input"))
    )
    (net (code "39") (name "GND") (class "Default")
      (node (ref "C416") (pin "1") (pinfunction "1_1") (pintype "passive"))
      (node (ref "C417") (pin "2") (pinfunction "2_2") (pintype "passive"))
      (node (ref "C418") (pin "1") (pinfunction "1_1") (pintype "passive"))
      (node (ref "C419") (pin "1") (pinfunction "1_1") (pintype "passive"))
      (node (ref "C420") (pin "1") (pinfunction "1_1") (pintype "passive"))
      (node (ref "C421") (pin "2") (pinfunction "2_2") (pintype "passive"))
      (node (ref "C422") (pin "2") (pinfunction "2_2") (pintype "passive"))
      (node (ref "C423") (pin "1") (pinfunction "1_1") (pintype "passive"))
      (node (ref "C424") (pin "2") (pinfunction "2_2") (pintype "passive"))
      (node (ref "C425") (pin "2") (pinfunction "2_2") (pintype "passive"))
      (node (ref "C426") (pin "1") (pinfunction "1_1") (pintype "passive"))
      (node (ref "C427") (pin "2") (pinfunction "2_2") (pintype "passive"))
      (node (ref "C428") (pin "1") (pinfunction "1_1") (pintype "passive"))
      (node (ref "C429") (pin "2") (pinfunction "2_2") (pintype "passive"))
      (node (ref "C430") (pin "2") (pinfunction "2_2") (pintype "passive"))
      (node (ref "C431") (pin "2") (pinfunction "2_2") (pintype "passive"))
      (node (ref "C432") (pin "2") (pinfunction "2_2") (pintype "passive"))
      (node (ref "C433") (pin "2") (pinfunction "2_2") (pintype "passive"))
      (node (ref "C434") (pin "2") (pinfunction "2_2") (pintype "passive"))
      (node (ref "C452") (pin "2") (pinfunction "2_2") (pintype "passive"))
      (node (ref "C453") (pin "1") (pinfunction "1_1") (pintype "passive"))
      (node (ref "C455a") (pin "1") (pinfunction "1_1") (pintype "passive"))
      (node (ref "C455b") (pin "1") (pinfunction "1_1") (pintype "passive"))
      (node (ref "C468") (pin "1") (pinfunction "1_1") (pintype "passive"))
      (node (ref "C584") (pin "2") (pinfunction "2_2") (pintype "passive"))
      (node (ref "C749") (pin "2") (pinfunction "2_2") (pintype "passive"))
      (node (ref "C750") (pin "2") (pinfunction "2_2") (pintype "passive"))
      (node (ref "C763") (pin "2") (pinfunction "2_2") (pintype "passive"))
      (node (ref "C765") (pin "1") (pinfunction "1_1") (pintype "passive"))
      (node (ref "C767") (pin "2") (pinfunction "2_2") (pintype "passive"))
      (node (ref "IC48") (pin "2") (pinfunction "GND_2") (pintype "power_in"))
      (node (ref "IC48") (pin "4") (pinfunction "GND_4") (pintype "power_in"))
      (node (ref "IC50") (pin "22") (pinfunction "GND1_22") (pintype "power_in"))
      (node (ref "IC50") (pin "33") (pinfunction "EP_33") (pintype "power_in"))
      (node (ref "IC51") (pin "2") (pinfunction "GND_2") (pintype "power_in"))
      (node (ref "IC52") (pin "8") (pinfunction "GND_8") (pintype "power_in"))
      (node (ref "IC53") (pin "8") (pinfunction "GND_8") (pintype "power_in"))
      (node (ref "IC54") (pin "3") (pinfunction "A_3") (pintype "passive"))
      (node (ref "J16") (pin "2") (pintype "passive"))
      (node (ref "J16") (pin "2a") (pinfunction "GND_2a") (pintype "passive"))
      (node (ref "J17") (pin "2") (pintype "passive"))
      (node (ref "J17") (pin "2a") (pinfunction "GND_2a") (pintype "passive"))
      (node (ref "J5") (pin "2") (pintype "passive"))
      (node (ref "J5") (pin "2a") (pinfunction "GND_2a") (pintype "passive"))
      (node (ref "OSC1") (pin "3") (pinfunction "GND_3") (pintype "power_in"))
      (node (ref "OSC2") (pin "3") (pinfunction "GND_3") (pintype "power_in"))
      (node (ref "OSC4") (pin "3") (pinfunction "GND_3") (pintype "power_in"))
      (node (ref "OSC5") (pin "2") (pinfunction "GND_2") (pintype "power_in"))
      (node (ref "Q8") (pin "2") (pinfunction "S_2") (pintype "passive"))
      (node (ref "R211") (pin "1") (pinfunction "1_1") (pintype "passive"))
      (node (ref "R215") (pin "1") (pinfunction "1_1") (pintype "passive"))
      (node (ref "R217") (pin "1") (pinfunction "1_1") (pintype "passive"))
      (node (ref "R245") (pin "1") (pinfunction "1_1") (pintype "passive"))
      (node (ref "R249") (pin "1") (pinfunction "1_1") (pintype "passive"))
      (node (ref "R250") (pin "1") (pinfunction "1_1") (pintype "passive"))
      (node (ref "R251") (pin "1") (pinfunction "1_1") (pintype "passive"))
      (node (ref "R252") (pin "1") (pinfunction "1_1") (pintype "passive"))
      (node (ref "R253") (pin "1") (pinfunction "1_1") (pintype "passive"))
      (node (ref "R254") (pin "1") (pinfunction "1_1") (pintype "passive"))
      (node (ref "R26") (pin "1") (pinfunction "1_1") (pintype "passive"))
    )
    (net (code "40") (name "Net-(C763-Pad1)") (class "Default")
      (node (ref "C763") (pin "1") (pinfunction "1_1") (pintype "passive"))
      (node (ref "R25") (pin "2") (pinfunction "2_2") (pintype "passive"))
      (node (ref "R26") (pin "2") (pinfunction "2_2") (pintype "passive"))
      (node (ref "R315") (pin "1") (pinfunction "1_1") (pintype "passive"))
      (node (ref "R316") (pin "1") (pinfunction "1_1") (pintype "passive"))
    )
    (net (code "41") (name "Net-(C764-Pad1)") (class "Default")
      (node (ref "C764") (pin "1") (pinfunction "1_1") (pintype "passive"))
      (node (ref "IC48") (pin "8") (pinfunction "IN_8") (pintype "input"))
      (node (ref "R315") (pin "2") (pinfunction "2_2") (pintype "passive"))
    )
    (net (code "42") (name "Net-(C764-Pad2)") (class "Default")
      (node (ref "C764") (pin "2") (pinfunction "2_2") (pintype "passive"))
      (node (ref "J5") (pin "1") (pintype "passive"))
      (node (ref "R211") (pin "2") (pinfunction "2_2") (pintype "passive"))
    )
    (net (code "43") (name "Net-(C765-Pad2)") (class "Default")
      (node (ref "C765") (pin "2") (pinfunction "2_2") (pintype "passive"))
      (node (ref "IC48") (pin "1") (pinfunction "IN_1") (pintype "input"))
      (node (ref "R316") (pin "2") (pinfunction "2_2") (pintype "passive"))
    )
    (net (code "44") (name "Net-(IC48-EN)") (class "Default")
      (node (ref "IC48") (pin "3") (pinfunction "EN_3") (pintype "input"))
      (node (ref "Q8") (pin "3") (pinfunction "D_3") (pintype "passive"))
      (node (ref "R317") (pin "1") (pinfunction "1_1") (pintype "passive"))
    )
    (net (code "45") (name "P3V3") (class "Default")
      (node (ref "L13") (pin "1") (pintype "passive"))
      (node (ref "R220") (pin "2") (pinfunction "2_2") (pintype "passive"))
      (node (ref "R223") (pin "2") (pinfunction "2_2") (pintype "passive"))
      (node (ref "R25") (pin "1") (pinfunction "1_1") (pintype "passive"))
      (node (ref "R272") (pin "2") (pinfunction "2_2") (pintype "passive"))
    )
    (net (code "46") (name "P3V3_CLEAN") (class "Default")
      (node (ref "C428") (pin "2") (pinfunction "2_2") (pintype "passive"))
      (node (ref "C429") (pin "1") (pinfunction "1_1") (pintype "passive"))
      (node (ref "C430") (pin "1") (pinfunction "1_1") (pintype "passive"))
      (node (ref "C431") (pin "1") (pinfunction "1_1") (pintype "passive"))
      (node (ref "C432") (pin "1") (pinfunction "1_1") (pintype "passive"))
      (node (ref "C433") (pin "1") (pinfunction "1_1") (pintype "passive"))
      (node (ref "C434") (pin "1") (pinfunction "1_1") (pintype "passive"))
      (node (ref "C455a") (pin "2") (pinfunction "2_2") (pintype "passive"))
      (node (ref "C455b") (pin "2") (pinfunction "2_2") (pintype "passive"))
      (node (ref "C468") (pin "2") (pinfunction "2_2") (pintype "passive"))
      (node (ref "C584") (pin "1") (pinfunction "1_1") (pintype "passive"))
      (node (ref "C749") (pin "1") (pinfunction "1_1") (pintype "passive"))
      (node (ref "C750") (pin "1") (pinfunction "1_1") (pintype "passive"))
      (node (ref "C767") (pin "1") (pinfunction "1_1") (pintype "passive"))
      (node (ref "IC48") (pin "7") (pinfunction "VCC_7") (pintype "power_in"))
      (node (ref "IC50") (pin "1") (pinfunction "VCCOUT_1") (pintype "power_in"))
      (node (ref "IC50") (pin "20") (pinfunction "VCCIN_20") (pintype "power_in"))
      (node (ref "IC50") (pin "27") (pinfunction "VCCOUT_27") (pintype "power_in"))
      (node (ref "IC50") (pin "30") (pinfunction "VCCOUT_30") (pintype "power_in"))
      (node (ref "IC50") (pin "4") (pinfunction "VCCOUT_4") (pintype "power_in"))
      (node (ref "IC50") (pin "7") (pinfunction "CE_7") (pintype "input"))
      (node (ref "IC50") (pin "9") (pinfunction "VCCVCO_9") (pintype "power_in"))
      (node (ref "IC51") (pin "1") (pinfunction "VIN_1") (pintype "power_in"))
      (node (ref "IC51") (pin "3") (pinfunction "EN_3") (pintype "input"))
      (node (ref "IC52") (pin "1") (pinfunction "VDD_1") (pintype "power_in"))
      (node (ref "IC53") (pin "1") (pinfunction "VDD_1") (pintype "power_in"))
      (node (ref "L13") (pin "2") (pintype "passive"))
      (node (ref "L21") (pin "2") (pinfunction "2_2") (pintype "passive"))
      (node (ref "L9") (pin "2") (pinfunction "2_2") (pintype "passive"))
      (node (ref "OSC2") (pin "2") (pinfunction "E/D_2") (pintype "input"))
      (node (ref "OSC2") (pin "6") (pinfunction "+VS_6") (pintype "power_in"))
      (node (ref "R219") (pin "1") (pinfunction "1_1") (pintype "passive"))
      (node (ref "R317") (pin "2") (pinfunction "2_2") (pintype "passive"))
    )
    (net (code "47") (name "unconnected-(IC50-NC-Pad8)") (class "Default")
      (node (ref "IC50") (pin "8") (pinfunction "NC_8") (pintype "passive"))
    )
    (net (code "48") (name "unconnected-(IC50-NC-Pad24)") (class "Default")
      (node (ref "IC50") (pin "24") (pinfunction "NC_24") (pintype "passive"))
    )
    (net (code "49") (name "unconnected-(IC50-OSCOUT-Pad23)") (class "Default")
      (node (ref "IC50") (pin "23") (pinfunction "OSCOUT_23") (pintype "output+no_connect"))
    )
    (net (code "50") (name "unconnected-(IC50-OUTN2-Pad31)") (class "Default")
      (node (ref "IC50") (pin "31") (pinfunction "OUTN2_31") (pintype "output+no_connect"))
    )
    (net (code "51") (name "unconnected-(IC50-OUTN3-Pad28)") (class "Default")
      (node (ref "IC50") (pin "28") (pinfunction "OUTN3_28") (pintype "output+no_connect"))
    )
    (net (code "52") (name "unconnected-(IC50-OUTP2-Pad32)") (class "Default")
      (node (ref "IC50") (pin "32") (pinfunction "OUTP2_32") (pintype "output+no_connect"))
    )
    (net (code "53") (name "unconnected-(IC50-OUTP3-Pad29)") (class "Default")
      (node (ref "IC50") (pin "29") (pinfunction "OUTP3_29") (pintype "output+no_connect"))
    )
    (net (code "54") (name "unconnected-(IC51-NC-Pad4)") (class "Default")
      (node (ref "IC51") (pin "4") (pinfunction "NC_4") (pintype "passive"))
    )
    (net (code "55") (name "unconnected-(OSC2-N{slash}C-Pad5)") (class "Default")
      (node (ref "OSC2") (pin "5") (pinfunction "N/C_5") (pintype "passive"))
    )
  )
)
